# GasSensorCentral_v1_0.net
KiCad netlist of a schematic drawn in EAGLE
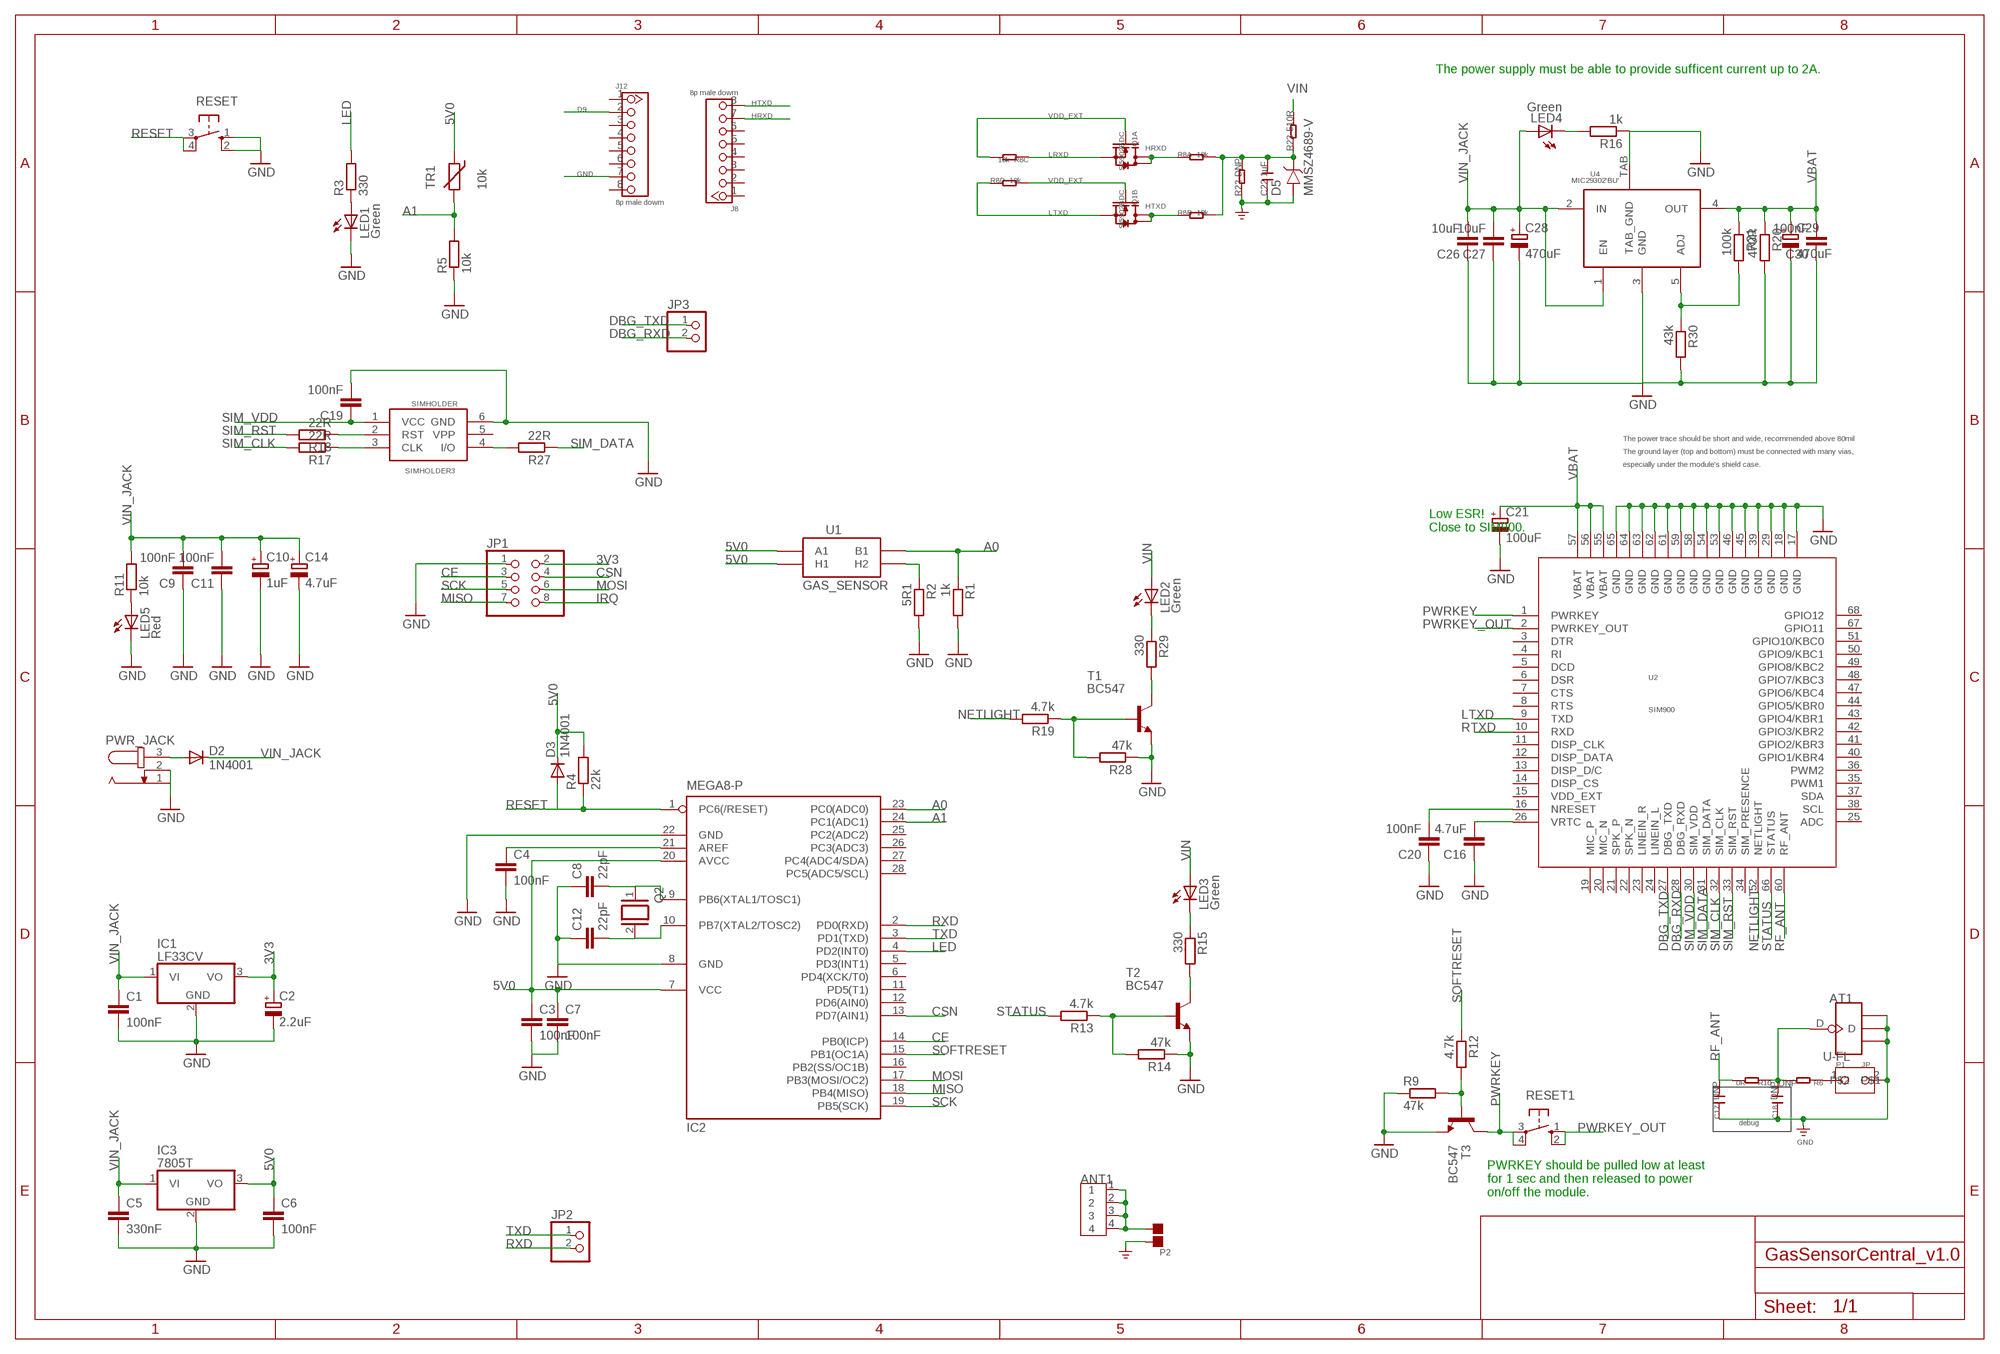
[diagram p0: schematic, sheet 1]

(export (version "E")
  (design (tool "Eeschema 10.0.6"))
  (components
    (comp (ref "ANT1")
      (value "ANTENNA-SMA-IPX")
      (footprint "eagle-import:SMA-TO-IPX")
      (libsource (lib "eagle-import") (part "ANTENNA-SMA-IPX"))
    )
    (comp (ref "AT1")
      (value "U-FL")
      (footprint "eagle-import:4P-U-FL")
      (libsource (lib "eagle-import") (part "ANTENNA-U-FL"))
    )
    (comp (ref "C1")
      (value "100nF")
      (footprint "eagle-import:C025-025X050")
      (libsource (lib "eagle-import") (part "C-EU025-025X050"))
    )
    (comp (ref "C2")
      (value "2.2uF")
      (footprint "eagle-import:E2,5-5")
      (libsource (lib "eagle-import") (part "CPOL-EUE2.5-5"))
    )
    (comp (ref "C3")
      (value "100nF")
      (footprint "eagle-import:C025-025X050")
      (libsource (lib "eagle-import") (part "C-EU025-025X050"))
    )
    (comp (ref "C4")
      (value "100nF")
      (footprint "eagle-import:C025-025X050")
      (libsource (lib "eagle-import") (part "C-EU025-025X050"))
    )
    (comp (ref "C5")
      (value "330nF")
      (footprint "eagle-import:C025-025X050")
      (libsource (lib "eagle-import") (part "C-EU025-025X050"))
    )
    (comp (ref "C6")
      (value "100nF")
      (footprint "eagle-import:C025-025X050")
      (libsource (lib "eagle-import") (part "C-EU025-025X050"))
    )
    (comp (ref "C7")
      (value "100nF")
      (footprint "eagle-import:C025-025X050")
      (libsource (lib "eagle-import") (part "C-EU025-025X050"))
    )
    (comp (ref "C8")
      (value "22pF")
      (footprint "eagle-import:C025-025X050")
      (libsource (lib "eagle-import") (part "C-EU025-025X050"))
    )
    (comp (ref "C9")
      (value "100nF")
      (footprint "eagle-import:C025-025X050")
      (libsource (lib "eagle-import") (part "C-EU025-025X050"))
    )
    (comp (ref "C10")
      (value "1uF")
      (footprint "eagle-import:E2,5-5")
      (libsource (lib "eagle-import") (part "CPOL-EUE2.5-5"))
    )
    (comp (ref "C11")
      (value "100nF")
      (footprint "eagle-import:C025-025X050")
      (libsource (lib "eagle-import") (part "C-EU025-025X050"))
    )
    (comp (ref "C12")
      (value "22pF")
      (footprint "eagle-import:C025-025X050")
      (libsource (lib "eagle-import") (part "C-EU025-025X050"))
    )
    (comp (ref "C14")
      (value "4.7uF")
      (footprint "eagle-import:E2,5-5")
      (libsource (lib "eagle-import") (part "CPOL-EUE2.5-5"))
    )
    (comp (ref "C16")
      (value "4.7uF")
      (footprint "eagle-import:C025-025X050")
      (libsource (lib "eagle-import") (part "C-EU025-025X050"))
    )
    (comp (ref "C17")
      (value "DNP")
      (footprint "eagle-import:0402")
      (libsource (lib "eagle-import") (part "C-0402"))
    )
    (comp (ref "C18")
      (value "DNP")
      (footprint "eagle-import:0402")
      (libsource (lib "eagle-import") (part "C-0402"))
    )
    (comp (ref "C19")
      (value "100nF")
      (footprint "eagle-import:C025-025X050")
      (libsource (lib "eagle-import") (part "C-EU025-025X050"))
    )
    (comp (ref "C20")
      (value "100nF")
      (footprint "eagle-import:C025-025X050")
      (libsource (lib "eagle-import") (part "C-EU025-025X050"))
    )
    (comp (ref "C21")
      (value "100uF")
      (footprint "eagle-import:E2,5-5")
      (libsource (lib "eagle-import") (part "CPOL-EUE2.5-5"))
    )
    (comp (ref "C22")
      (value "1uF")
      (footprint "eagle-import:0603")
      (libsource (lib "eagle-import") (part "C-0603"))
    )
    (comp (ref "C26")
      (value "10uF")
      (footprint "eagle-import:C025-025X050")
      (libsource (lib "eagle-import") (part "C-EU025-025X050"))
    )
    (comp (ref "C27")
      (value "10uF")
      (footprint "eagle-import:C025-025X050")
      (libsource (lib "eagle-import") (part "C-EU025-025X050"))
    )
    (comp (ref "C28")
      (value "470uF")
      (footprint "eagle-import:E2,5-5")
      (libsource (lib "eagle-import") (part "CPOL-EUE2.5-5"))
    )
    (comp (ref "C29")
      (value "470uF")
      (footprint "eagle-import:E2,5-5")
      (libsource (lib "eagle-import") (part "CPOL-EUE2.5-5"))
    )
    (comp (ref "C30")
      (value "100nF")
      (footprint "eagle-import:C025-025X050")
      (libsource (lib "eagle-import") (part "C-EU025-025X050"))
    )
    (comp (ref "D2")
      (value "1N4001")
      (footprint "eagle-import:DO41-10")
      (libsource (lib "eagle-import") (part "1N4004"))
    )
    (comp (ref "D3")
      (value "1N4001")
      (footprint "eagle-import:DO41-10")
      (libsource (lib "eagle-import") (part "1N4004"))
    )
    (comp (ref "D5")
      (value "MMSZ4689-V")
      (footprint "eagle-import:SOD123-2.7X1.6")
      (libsource (lib "eagle-import") (part "D-VOL'MMSZ4681'"))
    )
    (comp (ref "IC1")
      (value "LF33CV")
      (footprint "eagle-import:TO220H")
      (libsource (lib "eagle-import") (part "78T05"))
    )
    (comp (ref "IC2")
      (value "MEGA8-P")
      (footprint "eagle-import:DIL28-3")
      (libsource (lib "eagle-import") (part "MEGA8-P"))
    )
    (comp (ref "IC3")
      (value "7805T")
      (footprint "eagle-import:TO220H")
      (libsource (lib "eagle-import") (part "78T05"))
    )
    (comp (ref "J8")
      (value "8p male dowm")
      (footprint "eagle-import:CK_1X8")
      (libsource (lib "eagle-import") (part "CK_1X8DD"))
    )
    (comp (ref "J12")
      (value "8p male dowm")
      (footprint "eagle-import:CK_1X8")
      (libsource (lib "eagle-import") (part "CK_1X8DD"))
    )
    (comp (ref "JP1")
      (value "PINHD-2X4")
      (footprint "eagle-import:2X04")
      (libsource (lib "eagle-import") (part "PINHD-2X4"))
    )
    (comp (ref "JP2")
      (value "PINHD-1X2/90")
      (footprint "eagle-import:1X02_90")
      (libsource (lib "eagle-import") (part "PINHD-1X2/90"))
    )
    (comp (ref "JP3")
      (value "PINHD-1X2/90")
      (footprint "eagle-import:1X02_90")
      (libsource (lib "eagle-import") (part "PINHD-1X2/90"))
    )
    (comp (ref "LED1")
      (value "Green")
      (footprint "eagle-import:LED3MM")
      (libsource (lib "eagle-import") (part "LED3MM"))
    )
    (comp (ref "LED2")
      (value "Green")
      (footprint "eagle-import:LED3MM")
      (libsource (lib "eagle-import") (part "LED3MM"))
    )
    (comp (ref "LED3")
      (value "Green")
      (footprint "eagle-import:LED3MM")
      (libsource (lib "eagle-import") (part "LED3MM"))
    )
    (comp (ref "LED4")
      (value "Green")
      (footprint "eagle-import:LED3MM")
      (libsource (lib "eagle-import") (part "LED3MM"))
    )
    (comp (ref "LED5")
      (value "Red")
      (footprint "eagle-import:LED3MM")
      (libsource (lib "eagle-import") (part "LED3MM"))
    )
    (comp (ref "P1") (value "JP") (footprint "eagle-import:JP") (libsource (lib "eagle-import") (part "JP")))
    (comp (ref "P2")
      (value "PAD-JUMPER-2P")
      (footprint "eagle-import:2P-SMD-1.78X1.27")
      (fields (field (name "PARTNO") "DNP"))
      (libsource (lib "eagle-import") (part "PAD-JUMPER-2P"))
    )
    (comp (ref "PWR_JACK")
      (value "JACK-PLUG0")
      (footprint "eagle-import:SPC4077")
      (libsource (lib "eagle-import") (part "JACK-PLUG0"))
    )
    (comp (ref "Q1")
      (value "Si5902BDC")
      (footprint "eagle-import:1206-8")
      (libsource (lib "eagle-import") (part "010-DUAL-N-MOSFET_1206-8"))
    )
    (comp (ref "Q2")
      (value "XTAL/S")
      (footprint "eagle-import:QS")
      (libsource (lib "eagle-import") (part "XTAL/S"))
    )
    (comp (ref "R1")
      (value "1k")
      (footprint "eagle-import:0207_10")
      (libsource (lib "eagle-import") (part "R-EU_0207/10"))
    )
    (comp (ref "R2")
      (value "5R1")
      (footprint "eagle-import:0207_10")
      (libsource (lib "eagle-import") (part "R-EU_0207/10"))
    )
    (comp (ref "R3")
      (value "330")
      (footprint "eagle-import:0207_10")
      (libsource (lib "eagle-import") (part "R-EU_0207/10"))
    )
    (comp (ref "R4")
      (value "22k")
      (footprint "eagle-import:0207_10")
      (libsource (lib "eagle-import") (part "R-EU_0207/10"))
    )
    (comp (ref "R5")
      (value "10k")
      (footprint "eagle-import:0207_10")
      (libsource (lib "eagle-import") (part "R-EU_0207/10"))
    )
    (comp (ref "R6")
      (value "DNP")
      (footprint "eagle-import:0402")
      (libsource (lib "eagle-import") (part "R-0402"))
    )
    (comp (ref "R8")
      (value "10k")
      (footprint "eagle-import:1206-8-3.3X2.4")
      (libsource (lib "eagle-import") (part "R-4R-1206"))
    )
    (comp (ref "R9")
      (value "47k")
      (footprint "eagle-import:0207_10")
      (libsource (lib "eagle-import") (part "R-EU_0207/10"))
    )
    (comp (ref "R10")
      (value "0R")
      (footprint "eagle-import:0402")
      (libsource (lib "eagle-import") (part "R-0402"))
    )
    (comp (ref "R11")
      (value "10k")
      (footprint "eagle-import:0207_10")
      (libsource (lib "eagle-import") (part "R-EU_0207/10"))
    )
    (comp (ref "R12")
      (value "4.7k")
      (footprint "eagle-import:0207_10")
      (libsource (lib "eagle-import") (part "R-EU_0207/10"))
    )
    (comp (ref "R13")
      (value "4.7k")
      (footprint "eagle-import:0207_10")
      (libsource (lib "eagle-import") (part "R-EU_0207/10"))
    )
    (comp (ref "R14")
      (value "47k")
      (footprint "eagle-import:0207_10")
      (libsource (lib "eagle-import") (part "R-EU_0207/10"))
    )
    (comp (ref "R15")
      (value "330")
      (footprint "eagle-import:0207_10")
      (libsource (lib "eagle-import") (part "R-EU_0207/10"))
    )
    (comp (ref "R16")
      (value "1k")
      (footprint "eagle-import:0207_10")
      (libsource (lib "eagle-import") (part "R-EU_0207/10"))
    )
    (comp (ref "R17")
      (value "22R")
      (footprint "eagle-import:0207_10")
      (libsource (lib "eagle-import") (part "R-EU_0207/10"))
    )
    (comp (ref "R18")
      (value "22R")
      (footprint "eagle-import:0207_10")
      (libsource (lib "eagle-import") (part "R-EU_0207/10"))
    )
    (comp (ref "R19")
      (value "4.7k")
      (footprint "eagle-import:0207_10")
      (libsource (lib "eagle-import") (part "R-EU_0207/10"))
    )
    (comp (ref "R20")
      (value "470R")
      (footprint "eagle-import:0207_10")
      (libsource (lib "eagle-import") (part "R-EU_0207/10"))
    )
    (comp (ref "R21")
      (value "100k")
      (footprint "eagle-import:0207_10")
      (libsource (lib "eagle-import") (part "R-EU_0207/10"))
    )
    (comp (ref "R22")
      (value "DNP")
      (footprint "eagle-import:0603")
      (libsource (lib "eagle-import") (part "R-0603"))
    )
    (comp (ref "R23")
      (value "510R")
      (footprint "eagle-import:0603")
      (libsource (lib "eagle-import") (part "R-0603"))
    )
    (comp (ref "R27")
      (value "22R")
      (footprint "eagle-import:0207_10")
      (libsource (lib "eagle-import") (part "R-EU_0207/10"))
    )
    (comp (ref "R28")
      (value "47k")
      (footprint "eagle-import:0207_10")
      (libsource (lib "eagle-import") (part "R-EU_0207/10"))
    )
    (comp (ref "R29")
      (value "330")
      (footprint "eagle-import:0207_10")
      (libsource (lib "eagle-import") (part "R-EU_0207/10"))
    )
    (comp (ref "R30")
      (value "43k")
      (footprint "eagle-import:0207_10")
      (libsource (lib "eagle-import") (part "R-EU_0207/10"))
    )
    (comp (ref "RESET")
      (value "10-XX")
      (footprint "eagle-import:B3F-10XX")
      (fields (field (name "MPN") "B3F-1000"))
      (libsource (lib "eagle-import") (part "10-XX"))
    )
    (comp (ref "RESET1")
      (value "10-XX")
      (footprint "eagle-import:B3F-10XX")
      (fields (field (name "MPN") "B3F-1000"))
      (libsource (lib "eagle-import") (part "10-XX"))
    )
    (comp (ref "SIMHOLDER")
      (value "SIMHOLDER3")
      (footprint "eagle-import:SIMHOLDER3")
      (libsource (lib "eagle-import") (part "SIMHOLDER3"))
    )
    (comp (ref "T1")
      (value "BC547")
      (footprint "eagle-import:TO92")
      (libsource (lib "eagle-import") (part "BC547"))
    )
    (comp (ref "T2")
      (value "BC547")
      (footprint "eagle-import:TO92")
      (libsource (lib "eagle-import") (part "BC547"))
    )
    (comp (ref "T3")
      (value "BC547")
      (footprint "eagle-import:TO92")
      (libsource (lib "eagle-import") (part "BC547"))
    )
    (comp (ref "TR1")
      (value "10k")
      (footprint "eagle-import:RS-2,5")
      (libsource (lib "eagle-import") (part "THERMISTOR_R-2,5"))
    )
    (comp (ref "U1")
      (value "GAS_SENSOR")
      (footprint "eagle-import:MQ-3")
      (libsource (lib "eagle-import") (part "GAS_SENSOR"))
    )
    (comp (ref "U2")
      (value "SIM900")
      (footprint "eagle-import:SIM900")
      (libsource (lib "eagle-import") (part "SIM900"))
    )
    (comp (ref "U4")
      (value "MIC29302'BU'")
      (footprint "eagle-import:TO-263")
      (libsource (lib "eagle-import") (part "MIC29302'BU'"))
    )
  )
  (nets
    (net (code "1") (name "/3V3") (class "Default")
      (node (ref "C2") (pin "+") (pinfunction "+_+") (pintype "passive"))
      (node (ref "IC1") (pin "3") (pinfunction "VO_3") (pintype "passive"))
      (node (ref "JP1") (pin "2") (pinfunction "2_2") (pintype "passive"))
    )
    (net (code "2") (name "/5V0") (class "Default")
      (node (ref "C3") (pin "1") (pinfunction "1_1") (pintype "passive"))
      (node (ref "C6") (pin "1") (pinfunction "1_1") (pintype "passive"))
      (node (ref "C7") (pin "1") (pinfunction "1_1") (pintype "passive"))
      (node (ref "D3") (pin "C") (pinfunction "C_C") (pintype "passive"))
      (node (ref "IC2") (pin "20") (pinfunction "AVCC_20") (pintype "power_in"))
      (node (ref "IC2") (pin "7") (pinfunction "VCC_7") (pintype "power_in"))
      (node (ref "IC3") (pin "3") (pinfunction "VO_3") (pintype "passive"))
      (node (ref "R4") (pin "2") (pinfunction "2_2") (pintype "passive"))
      (node (ref "TR1") (pin "1") (pinfunction "1_1") (pintype "passive"))
      (node (ref "U1") (pin "A1") (pinfunction "A1_A1") (pintype "bidirectional"))
      (node (ref "U1") (pin "HA") (pinfunction "H1_HA") (pintype "bidirectional"))
    )
    (net (code "3") (name "/A0") (class "Default")
      (node (ref "IC2") (pin "23") (pinfunction "PC0(ADC0)_23") (pintype "bidirectional"))
      (node (ref "R1") (pin "1") (pinfunction "1_1") (pintype "passive"))
      (node (ref "U1") (pin "B1") (pinfunction "B1_B1") (pintype "bidirectional"))
    )
    (net (code "4") (name "/A1") (class "Default")
      (node (ref "IC2") (pin "24") (pinfunction "PC1(ADC1)_24") (pintype "bidirectional"))
      (node (ref "R5") (pin "2") (pinfunction "2_2") (pintype "passive"))
      (node (ref "TR1") (pin "2") (pinfunction "2_2") (pintype "passive"))
    )
    (net (code "5") (name "/CE") (class "Default")
      (node (ref "IC2") (pin "14") (pinfunction "PB0(ICP)_14") (pintype "bidirectional"))
      (node (ref "JP1") (pin "3") (pinfunction "3_3") (pintype "passive"))
    )
    (net (code "6") (name "/CSN") (class "Default")
      (node (ref "IC2") (pin "13") (pinfunction "PD7(AIN1)_13") (pintype "bidirectional"))
      (node (ref "JP1") (pin "4") (pinfunction "4_4") (pintype "passive"))
    )
    (net (code "7") (name "/D9") (class "Default")
      (node (ref "J12") (pin "2") (pinfunction "P$2_2") (pintype "bidirectional"))
    )
    (net (code "8") (name "/DBG_RXD") (class "Default")
      (node (ref "JP3") (pin "2") (pinfunction "2_2") (pintype "passive"))
      (node (ref "U2") (pin "28") (pinfunction "DBG_RXD_28") (pintype "input"))
    )
    (net (code "9") (name "/DBG_TXD") (class "Default")
      (node (ref "JP3") (pin "1") (pinfunction "1_1") (pintype "passive"))
      (node (ref "U2") (pin "27") (pinfunction "DBG_TXD_27") (pintype "output"))
    )
    (net (code "10") (name "/HRXD") (class "Default")
      (node (ref "J8") (pin "7") (pinfunction "P$7_7") (pintype "bidirectional"))
      (node (ref "Q1") (pin "7") (pinfunction "D_7") (pintype "passive"))
      (node (ref "Q1") (pin "8") (pinfunction "D_8") (pintype "passive"))
      (node (ref "R8") (pin "1") (pinfunction "1_1") (pintype "passive"))
    )
    (net (code "11") (name "/HTXD") (class "Default")
      (node (ref "J8") (pin "8") (pinfunction "P$8_8") (pintype "bidirectional"))
      (node (ref "Q1") (pin "5") (pinfunction "D_5") (pintype "passive"))
      (node (ref "Q1") (pin "6") (pinfunction "D_6") (pintype "passive"))
      (node (ref "R8") (pin "2") (pinfunction "1_2") (pintype "passive"))
    )
    (net (code "12") (name "/IRQ") (class "Default")
      (node (ref "JP1") (pin "8") (pinfunction "8_8") (pintype "passive"))
    )
    (net (code "13") (name "/LED") (class "Default")
      (node (ref "IC2") (pin "4") (pinfunction "PD2(INT0)_4") (pintype "bidirectional"))
      (node (ref "R3") (pin "2") (pinfunction "2_2") (pintype "passive"))
    )
    (net (code "14") (name "/LRXD") (class "Default")
      (node (ref "Q1") (pin "1") (pinfunction "S_1") (pintype "passive"))
      (node (ref "R8") (pin "3") (pinfunction "1_3") (pintype "passive"))
    )
    (net (code "15") (name "/LTXD") (class "Default")
      (node (ref "Q1") (pin "3") (pinfunction "S_3") (pintype "passive"))
      (node (ref "R8") (pin "4") (pinfunction "1_4") (pintype "passive"))
      (node (ref "U2") (pin "9") (pinfunction "TXD_9") (pintype "output"))
    )
    (net (code "16") (name "/MISO") (class "Default")
      (node (ref "IC2") (pin "18") (pinfunction "PB4(MISO)_18") (pintype "bidirectional"))
      (node (ref "JP1") (pin "7") (pinfunction "7_7") (pintype "passive"))
    )
    (net (code "17") (name "/MOSI") (class "Default")
      (node (ref "IC2") (pin "17") (pinfunction "PB3(MOSI/OC2)_17") (pintype "bidirectional"))
      (node (ref "JP1") (pin "6") (pinfunction "6_6") (pintype "passive"))
    )
    (net (code "18") (name "/NETLIGHT") (class "Default")
      (node (ref "R19") (pin "2") (pinfunction "2_2") (pintype "passive"))
      (node (ref "U2") (pin "52") (pinfunction "NETLIGHT_52") (pintype "output"))
    )
    (net (code "19") (name "/PWRKEY") (class "Default")
      (node (ref "RESET1") (pin "3") (pinfunction "P_3") (pintype "passive"))
      (node (ref "RESET1") (pin "4") (pinfunction "P1_4") (pintype "passive"))
      (node (ref "T3") (pin "3") (pinfunction "C_3") (pintype "passive"))
      (node (ref "U2") (pin "1") (pinfunction "PWRKEY_1") (pintype "input"))
    )
    (net (code "20") (name "/PWRKEY_OUT") (class "Default")
      (node (ref "RESET1") (pin "1") (pinfunction "S_1") (pintype "passive"))
      (node (ref "RESET1") (pin "2") (pinfunction "S1_2") (pintype "passive"))
      (node (ref "U2") (pin "2") (pinfunction "PWRKEY_OUT_2") (pintype "output"))
    )
    (net (code "21") (name "/RESET") (class "Default")
      (node (ref "D3") (pin "A") (pinfunction "A_A") (pintype "passive"))
      (node (ref "IC2") (pin "1") (pinfunction "PC6(/RESET)_1") (pintype "bidirectional"))
      (node (ref "R4") (pin "1") (pinfunction "1_1") (pintype "passive"))
      (node (ref "RESET") (pin "3") (pinfunction "P_3") (pintype "passive"))
      (node (ref "RESET") (pin "4") (pinfunction "P1_4") (pintype "passive"))
    )
    (net (code "22") (name "/RF_ANT") (class "Default")
      (node (ref "C17") (pin "2") (pinfunction "2_2") (pintype "passive"))
      (node (ref "R10") (pin "2") (pinfunction "2_2") (pintype "passive"))
      (node (ref "U2") (pin "60") (pinfunction "RF_ANT_60") (pintype "bidirectional"))
    )
    (net (code "23") (name "/RTXD") (class "Default")
      (node (ref "U2") (pin "10") (pinfunction "RXD_10") (pintype "input"))
    )
    (net (code "24") (name "/RXD") (class "Default")
      (node (ref "IC2") (pin "2") (pinfunction "PD0(RXD)_2") (pintype "bidirectional"))
      (node (ref "JP2") (pin "2") (pinfunction "2_2") (pintype "passive"))
    )
    (net (code "25") (name "/SCK") (class "Default")
      (node (ref "IC2") (pin "19") (pinfunction "PB5(SCK)_19") (pintype "bidirectional"))
      (node (ref "JP1") (pin "5") (pinfunction "5_5") (pintype "passive"))
    )
    (net (code "26") (name "/SIM_CLK") (class "Default")
      (node (ref "R17") (pin "2") (pinfunction "2_2") (pintype "passive"))
      (node (ref "U2") (pin "32") (pinfunction "SIM_CLK_32") (pintype "output"))
    )
    (net (code "27") (name "/SIM_DATA") (class "Default")
      (node (ref "R27") (pin "1") (pinfunction "1_1") (pintype "passive"))
      (node (ref "U2") (pin "31") (pinfunction "SIM_DATA_31") (pintype "bidirectional"))
    )
    (net (code "28") (name "/SIM_RST") (class "Default")
      (node (ref "R18") (pin "2") (pinfunction "2_2") (pintype "passive"))
      (node (ref "U2") (pin "33") (pinfunction "SIM_RST_33") (pintype "output"))
    )
    (net (code "29") (name "/SIM_VDD") (class "Default")
      (node (ref "C19") (pin "1") (pinfunction "1_1") (pintype "passive"))
      (node (ref "SIMHOLDER") (pin "1") (pinfunction "VCC_1") (pintype "bidirectional"))
      (node (ref "U2") (pin "30") (pinfunction "SIM_VDD_30") (pintype "output"))
    )
    (net (code "30") (name "/SOFTRESET") (class "Default")
      (node (ref "IC2") (pin "15") (pinfunction "PB1(OC1A)_15") (pintype "bidirectional"))
      (node (ref "R12") (pin "1") (pinfunction "1_1") (pintype "passive"))
    )
    (net (code "31") (name "/STATUS") (class "Default")
      (node (ref "R13") (pin "2") (pinfunction "2_2") (pintype "passive"))
      (node (ref "U2") (pin "66") (pinfunction "STATUS_66") (pintype "output"))
    )
    (net (code "32") (name "/TXD") (class "Default")
      (node (ref "IC2") (pin "3") (pinfunction "PD1(TXD)_3") (pintype "bidirectional"))
      (node (ref "JP2") (pin "1") (pinfunction "1_1") (pintype "passive"))
    )
    (net (code "33") (name "/VBAT") (class "Default")
      (node (ref "C21") (pin "+") (pinfunction "+_+") (pintype "passive"))
      (node (ref "C29") (pin "+") (pinfunction "+_+") (pintype "passive"))
      (node (ref "C30") (pin "2") (pinfunction "2_2") (pintype "passive"))
      (node (ref "R20") (pin "1") (pinfunction "1_1") (pintype "passive"))
      (node (ref "R21") (pin "1") (pinfunction "1_1") (pintype "passive"))
      (node (ref "U2") (pin "55") (pinfunction "VBAT_55") (pintype "power_in"))
      (node (ref "U2") (pin "56") (pinfunction "VBAT_56") (pintype "power_in"))
      (node (ref "U2") (pin "57") (pinfunction "VBAT_57") (pintype "power_in"))
      (node (ref "U4") (pin "4") (pinfunction "OUT_4") (pintype "bidirectional"))
    )
    (net (code "34") (name "/VDD_EXT") (class "Default")
      (node (ref "Q1") (pin "2") (pinfunction "G_2") (pintype "passive"))
      (node (ref "Q1") (pin "4") (pinfunction "G_4") (pintype "passive"))
      (node (ref "R8") (pin "5") (pinfunction "2_5") (pintype "passive"))
      (node (ref "R8") (pin "6") (pinfunction "2_6") (pintype "passive"))
    )
    (net (code "35") (name "/VIN") (class "Default")
      (node (ref "LED2") (pin "A") (pinfunction "A_A") (pintype "passive"))
      (node (ref "LED3") (pin "A") (pinfunction "A_A") (pintype "passive"))
      (node (ref "R23") (pin "2") (pinfunction "2_2") (pintype "passive"))
    )
    (net (code "36") (name "/VIN_JACK") (class "Default")
      (node (ref "C1") (pin "1") (pinfunction "1_1") (pintype "passive"))
      (node (ref "C10") (pin "+") (pinfunction "+_+") (pintype "passive"))
      (node (ref "C11") (pin "2") (pinfunction "2_2") (pintype "passive"))
      (node (ref "C14") (pin "+") (pinfunction "+_+") (pintype "passive"))
      (node (ref "C26") (pin "2") (pinfunction "2_2") (pintype "passive"))
      (node (ref "C27") (pin "2") (pinfunction "2_2") (pintype "passive"))
      (node (ref "C28") (pin "+") (pinfunction "+_+") (pintype "passive"))
      (node (ref "C5") (pin "1") (pinfunction "1_1") (pintype "passive"))
      (node (ref "C9") (pin "2") (pinfunction "2_2") (pintype "passive"))
      (node (ref "D2") (pin "C") (pinfunction "C_C") (pintype "passive"))
      (node (ref "IC1") (pin "1") (pinfunction "VI_1") (pintype "input"))
      (node (ref "IC3") (pin "1") (pinfunction "VI_1") (pintype "input"))
      (node (ref "LED4") (pin "A") (pinfunction "A_A") (pintype "passive"))
      (node (ref "R11") (pin "2") (pinfunction "2_2") (pintype "passive"))
      (node (ref "U4") (pin "1") (pinfunction "EN_1") (pintype "bidirectional"))
      (node (ref "U4") (pin "2") (pinfunction "IN_2") (pintype "bidirectional"))
    )
    (net (code "37") (name "GND") (class "Default")
      (node (ref "AT1") (pin "GND1") (pinfunction "GND1_GND1") (pintype "bidirectional"))
      (node (ref "AT1") (pin "GND2") (pinfunction "GND2_GND2") (pintype "bidirectional"))
      (node (ref "AT1") (pin "GND3") (pinfunction "GND3_GND3") (pintype "bidirectional"))
      (node (ref "C1") (pin "2") (pinfunction "2_2") (pintype "passive"))
      (node (ref "C10") (pin "-") (pinfunction "-_-") (pintype "passive"))
      (node (ref "C11") (pin "1") (pinfunction "1_1") (pintype "passive"))
      (node (ref "C12") (pin "1") (pinfunction "1_1") (pintype "passive"))
      (node (ref "C14") (pin "-") (pinfunction "-_-") (pintype "passive"))
      (node (ref "C16") (pin "1") (pinfunction "1_1") (pintype "passive"))
      (node (ref "C17") (pin "1") (pinfunction "1_1") (pintype "passive"))
      (node (ref "C18") (pin "1") (pinfunction "1_1") (pintype "passive"))
      (node (ref "C19") (pin "2") (pinfunction "2_2") (pintype "passive"))
      (node (ref "C2") (pin "-") (pinfunction "-_-") (pintype "passive"))
      (node (ref "C20") (pin "1") (pinfunction "1_1") (pintype "passive"))
      (node (ref "C21") (pin "-") (pinfunction "-_-") (pintype "passive"))
      (node (ref "C22") (pin "1") (pinfunction "1_1") (pintype "passive"))
      (node (ref "C26") (pin "1") (pinfunction "1_1") (pintype "passive"))
      (node (ref "C27") (pin "1") (pinfunction "1_1") (pintype "passive"))
      (node (ref "C28") (pin "-") (pinfunction "-_-") (pintype "passive"))
      (node (ref "C29") (pin "-") (pinfunction "-_-") (pintype "passive"))
      (node (ref "C3") (pin "2") (pinfunction "2_2") (pintype "passive"))
      (node (ref "C30") (pin "1") (pinfunction "1_1") (pintype "passive"))
      (node (ref "C4") (pin "2") (pinfunction "2_2") (pintype "passive"))
      (node (ref "C5") (pin "2") (pinfunction "2_2") (pintype "passive"))
      (node (ref "C6") (pin "2") (pinfunction "2_2") (pintype "passive"))
      (node (ref "C7") (pin "2") (pinfunction "2_2") (pintype "passive"))
      (node (ref "C8") (pin "1") (pinfunction "1_1") (pintype "passive"))
      (node (ref "C9") (pin "1") (pinfunction "1_1") (pintype "passive"))
      (node (ref "D5") (pin "1") (pinfunction "1_1") (pintype "bidirectional"))
      (node (ref "IC1") (pin "2") (pinfunction "GND_2") (pintype "passive"))
      (node (ref "IC2") (pin "22") (pinfunction "GND_22") (pintype "power_in"))
      (node (ref "IC2") (pin "8") (pinfunction "GND_8") (pintype "power_in"))
      (node (ref "IC3") (pin "2") (pinfunction "GND_2") (pintype "passive"))
      (node (ref "J12") (pin "7") (pinfunction "P$7_7") (pintype "bidirectional"))
      (node (ref "JP1") (pin "1") (pinfunction "1_1") (pintype "passive"))
      (node (ref "LED1") (pin "K") (pinfunction "C_K") (pintype "passive"))
      (node (ref "LED5") (pin "K") (pinfunction "C_K") (pintype "passive"))
      (node (ref "P1") (pin "2") (pinfunction "P$2_2") (pintype "bidirectional"))
      (node (ref "P2") (pin "2") (pinfunction "2_2") (pintype "bidirectional"))
      (node (ref "PWR_JACK") (pin "1") (pinfunction "1_1") (pintype "passive"))
      (node (ref "PWR_JACK") (pin "2") (pinfunction "2_2") (pintype "passive"))
      (node (ref "R1") (pin "2") (pinfunction "2_2") (pintype "passive"))
      (node (ref "R14") (pin "1") (pinfunction "1_1") (pintype "passive"))
      (node (ref "R16") (pin "1") (pinfunction "1_1") (pintype "passive"))
      (node (ref "R2") (pin "2") (pinfunction "2_2") (pintype "passive"))
      (node (ref "R20") (pin "2") (pinfunction "2_2") (pintype "passive"))
      (node (ref "R22") (pin "1") (pinfunction "1_1") (pintype "passive"))
      (node (ref "R28") (pin "1") (pinfunction "1_1") (pintype "passive"))
      (node (ref "R30") (pin "2") (pinfunction "2_2") (pintype "passive"))
      (node (ref "R5") (pin "1") (pinfunction "1_1") (pintype "passive"))
      (node (ref "R9") (pin "1") (pinfunction "1_1") (pintype "passive"))
      (node (ref "RESET") (pin "1") (pinfunction "S_1") (pintype "passive"))
      (node (ref "RESET") (pin "2") (pinfunction "S1_2") (pintype "passive"))
      (node (ref "SIMHOLDER") (pin "6") (pinfunction "GND_6") (pintype "bidirectional"))
      (node (ref "T1") (pin "1") (pinfunction "E_1") (pintype "passive"))
      (node (ref "T2") (pin "1") (pinfunction "E_1") (pintype "passive"))
      (node (ref "T3") (pin "1") (pinfunction "E_1") (pintype "passive"))
      (node (ref "U2") (pin "17") (pinfunction "GND_17") (pintype "power_in"))
      (node (ref "U2") (pin "18") (pinfunction "GND_18") (pintype "power_in"))
      (node (ref "U2") (pin "29") (pinfunction "GND_29") (pintype "power_in"))
      (node (ref "U2") (pin "39") (pinfunction "GND_39") (pintype "power_in"))
      (node (ref "U2") (pin "45") (pinfunction "GND_45") (pintype "power_in"))
      (node (ref "U2") (pin "46") (pinfunction "GND_46") (pintype "power_in"))
      (node (ref "U2") (pin "53") (pinfunction "GND_53") (pintype "power_in"))
      (node (ref "U2") (pin "54") (pinfunction "GND_54") (pintype "power_in"))
      (node (ref "U2") (pin "58") (pinfunction "GND_58") (pintype "power_in"))
      (node (ref "U2") (pin "59") (pinfunction "GND_59") (pintype "power_in"))
      (node (ref "U2") (pin "61") (pinfunction "GND_61") (pintype "power_in"))
      (node (ref "U2") (pin "62") (pinfunction "GND_62") (pintype "power_in"))
      (node (ref "U2") (pin "63") (pinfunction "GND_63") (pintype "power_in"))
      (node (ref "U2") (pin "64") (pinfunction "GND_64") (pintype "power_in"))
      (node (ref "U2") (pin "65") (pinfunction "GND_65") (pintype "power_in"))
      (node (ref "U4") (pin "3") (pinfunction "GND_3") (pintype "bidirectional"))
      (node (ref "U4") (pin "TAB") (pinfunction "TAB_GND_TAB") (pintype "bidirectional"))
    )
    (net (code "38") (name "Net-(ANT1-Pad1)") (class "Default")
      (node (ref "ANT1") (pin "1") (pinfunction "1_1") (pintype "bidirectional"))
      (node (ref "ANT1") (pin "2") (pinfunction "2_2") (pintype "bidirectional"))
      (node (ref "ANT1") (pin "3") (pinfunction "3_3") (pintype "bidirectional"))
      (node (ref "ANT1") (pin "4") (pinfunction "4_4") (pintype "bidirectional"))
      (node (ref "P2") (pin "1") (pinfunction "1_1") (pintype "bidirectional"))
    )
    (net (code "39") (name "Net-(AT1-PadD)") (class "Default")
      (node (ref "AT1") (pin "D") (pinfunction "D_D") (pintype "bidirectional"))
      (node (ref "C18") (pin "2") (pinfunction "2_2") (pintype "passive"))
      (node (ref "R10") (pin "1") (pinfunction "1_1") (pintype "passive"))
      (node (ref "R6") (pin "2") (pinfunction "2_2") (pintype "passive"))
    )
    (net (code "40") (name "Net-(D2-PadA)") (class "Default")
      (node (ref "D2") (pin "A") (pinfunction "A_A") (pintype "passive"))
      (node (ref "PWR_JACK") (pin "3") (pinfunction "3_3") (pintype "passive"))
    )
    (net (code "41") (name "Net-(IC2-AREF)") (class "Default")
      (node (ref "C4") (pin "1") (pinfunction "1_1") (pintype "passive"))
      (node (ref "IC2") (pin "21") (pinfunction "AREF_21") (pintype "passive"))
    )
    (net (code "42") (name "Net-(IC2-PB6(XTAL1{slash}TOSC1))") (class "Default")
      (node (ref "C8") (pin "2") (pinfunction "2_2") (pintype "passive"))
      (node (ref "IC2") (pin "9") (pinfunction "PB6(XTAL1/TOSC1)_9") (pintype "bidirectional"))
      (node (ref "Q2") (pin "1") (pinfunction "1_1") (pintype "passive"))
    )
    (net (code "43") (name "Net-(IC2-PB7(XTAL2{slash}TOSC2))") (class "Default")
      (node (ref "C12") (pin "2") (pinfunction "2_2") (pintype "passive"))
      (node (ref "IC2") (pin "10") (pinfunction "PB7(XTAL2/TOSC2)_10") (pintype "bidirectional"))
      (node (ref "Q2") (pin "2") (pinfunction "2_2") (pintype "passive"))
    )
    (net (code "44") (name "Net-(LED1-PadA)") (class "Default")
      (node (ref "LED1") (pin "A") (pinfunction "A_A") (pintype "passive"))
      (node (ref "R3") (pin "1") (pinfunction "1_1") (pintype "passive"))
    )
    (net (code "45") (name "Net-(LED2-C)") (class "Default")
      (node (ref "LED2") (pin "K") (pinfunction "C_K") (pintype "passive"))
      (node (ref "R29") (pin "1") (pinfunction "1_1") (pintype "passive"))
    )
    (net (code "46") (name "Net-(LED3-C)") (class "Default")
      (node (ref "LED3") (pin "K") (pinfunction "C_K") (pintype "passive"))
      (node (ref "R15") (pin "1") (pinfunction "1_1") (pintype "passive"))
    )
    (net (code "47") (name "Net-(LED4-C)") (class "Default")
      (node (ref "LED4") (pin "K") (pinfunction "C_K") (pintype "passive"))
      (node (ref "R16") (pin "2") (pinfunction "2_2") (pintype "passive"))
    )
    (net (code "48") (name "Net-(LED5-PadA)") (class "Default")
      (node (ref "LED5") (pin "A") (pinfunction "A_A") (pintype "passive"))
      (node (ref "R11") (pin "1") (pinfunction "1_1") (pintype "passive"))
    )
    (net (code "49") (name "Net-(P1-P$1)") (class "Default")
      (node (ref "P1") (pin "1") (pinfunction "P$1_1") (pintype "bidirectional"))
      (node (ref "R6") (pin "1") (pinfunction "1_1") (pintype "passive"))
    )
    (net (code "50") (name "Net-(R8A-2)") (class "Default")
      (node (ref "C22") (pin "2") (pinfunction "2_2") (pintype "passive"))
      (node (ref "D5") (pin "2") (pinfunction "2_2") (pintype "bidirectional"))
      (node (ref "R22") (pin "2") (pinfunction "2_2") (pintype "passive"))
      (node (ref "R23") (pin "1") (pinfunction "1_1") (pintype "passive"))
      (node (ref "R8") (pin "7") (pinfunction "2_7") (pintype "passive"))
      (node (ref "R8") (pin "8") (pinfunction "2_8") (pintype "passive"))
    )
    (net (code "51") (name "Net-(SIMHOLDER-CLK)") (class "Default")
      (node (ref "R17") (pin "1") (pinfunction "1_1") (pintype "passive"))
      (node (ref "SIMHOLDER") (pin "3") (pinfunction "CLK_3") (pintype "bidirectional"))
    )
    (net (code "52") (name "Net-(SIMHOLDER-I{slash}O)") (class "Default")
      (node (ref "R27") (pin "2") (pinfunction "2_2") (pintype "passive"))
      (node (ref "SIMHOLDER") (pin "4") (pinfunction "I/O_4") (pintype "bidirectional"))
    )
    (net (code "53") (name "Net-(SIMHOLDER-RST)") (class "Default")
      (node (ref "R18") (pin "1") (pinfunction "1_1") (pintype "passive"))
      (node (ref "SIMHOLDER") (pin "2") (pinfunction "RST_2") (pintype "bidirectional"))
    )
    (net (code "54") (name "Net-(T1-B)") (class "Default")
      (node (ref "R19") (pin "1") (pinfunction "1_1") (pintype "passive"))
      (node (ref "R28") (pin "2") (pinfunction "2_2") (pintype "passive"))
      (node (ref "T1") (pin "2") (pinfunction "B_2") (pintype "passive"))
    )
    (net (code "55") (name "Net-(T1-C)") (class "Default")
      (node (ref "R29") (pin "2") (pinfunction "2_2") (pintype "passive"))
      (node (ref "T1") (pin "3") (pinfunction "C_3") (pintype "passive"))
    )
    (net (code "56") (name "Net-(T2-B)") (class "Default")
      (node (ref "R13") (pin "1") (pinfunction "1_1") (pintype "passive"))
      (node (ref "R14") (pin "2") (pinfunction "2_2") (pintype "passive"))
      (node (ref "T2") (pin "2") (pinfunction "B_2") (pintype "passive"))
    )
    (net (code "57") (name "Net-(T2-C)") (class "Default")
      (node (ref "R15") (pin "2") (pinfunction "2_2") (pintype "passive"))
      (node (ref "T2") (pin "3") (pinfunction "C_3") (pintype "passive"))
    )
    (net (code "58") (name "Net-(T3-B)") (class "Default")
      (node (ref "R12") (pin "2") (pinfunction "2_2") (pintype "passive"))
      (node (ref "R9") (pin "2") (pinfunction "2_2") (pintype "passive"))
      (node (ref "T3") (pin "2") (pinfunction "B_2") (pintype "passive"))
    )
    (net (code "59") (name "Net-(U1-H2)") (class "Default")
      (node (ref "R2") (pin "1") (pinfunction "1_1") (pintype "passive"))
      (node (ref "U1") (pin "HB") (pinfunction "H2_HB") (pintype "bidirectional"))
    )
    (net (code "60") (name "Net-(U2-NRESET)") (class "Default")
      (node (ref "C20") (pin "2") (pinfunction "2_2") (pintype "passive"))
      (node (ref "U2") (pin "16") (pinfunction "NRESET_16") (pintype "input"))
    )
    (net (code "61") (name "Net-(U2-VRTC)") (class "Default")
      (node (ref "C16") (pin "2") (pinfunction "2_2") (pintype "passive"))
      (node (ref "U2") (pin "26") (pinfunction "VRTC_26") (pintype "bidirectional"))
    )
    (net (code "62") (name "Net-(U4-ADJ)") (class "Default")
      (node (ref "R21") (pin "2") (pinfunction "2_2") (pintype "passive"))
      (node (ref "R30") (pin "1") (pinfunction "1_1") (pintype "passive"))
      (node (ref "U4") (pin "5") (pinfunction "ADJ_5") (pintype "bidirectional"))
    )
    (net (code "63") (name "unconnected-(IC2-PB2(SS{slash}OC1B)-Pad16)") (class "Default")
      (node (ref "IC2") (pin "16") (pinfunction "PB2(SS/OC1B)_16") (pintype "bidirectional"))
    )
    (net (code "64") (name "unconnected-(IC2-PC2(ADC2)-Pad25)") (class "Default")
      (node (ref "IC2") (pin "25") (pinfunction "PC2(ADC2)_25") (pintype "bidirectional"))
    )
    (net (code "65") (name "unconnected-(IC2-PC3(ADC3)-Pad26)") (class "Default")
      (node (ref "IC2") (pin "26") (pinfunction "PC3(ADC3)_26") (pintype "bidirectional"))
    )
    (net (code "66") (name "unconnected-(IC2-PC4(ADC4{slash}SDA)-Pad27)") (class "Default")
      (node (ref "IC2") (pin "27") (pinfunction "PC4(ADC4/SDA)_27") (pintype "bidirectional"))
    )
    (net (code "67") (name "unconnected-(IC2-PC5(ADC5{slash}SCL)-Pad28)") (class "Default")
      (node (ref "IC2") (pin "28") (pinfunction "PC5(ADC5/SCL)_28") (pintype "bidirectional"))
    )
    (net (code "68") (name "unconnected-(IC2-PD3(INT1)-Pad5)") (class "Default")
      (node (ref "IC2") (pin "5") (pinfunction "PD3(INT1)_5") (pintype "bidirectional"))
    )
    (net (code "69") (name "unconnected-(IC2-PD4(XCK{slash}T0)-Pad6)") (class "Default")
      (node (ref "IC2") (pin "6") (pinfunction "PD4(XCK/T0)_6") (pintype "bidirectional"))
    )
    (net (code "70") (name "unconnected-(IC2-PD5(T1)-Pad11)") (class "Default")
      (node (ref "IC2") (pin "11") (pinfunction "PD5(T1)_11") (pintype "bidirectional"))
    )
    (net (code "71") (name "unconnected-(IC2-PD6(AIN0)-Pad12)") (class "Default")
      (node (ref "IC2") (pin "12") (pinfunction "PD6(AIN0)_12") (pintype "bidirectional"))
    )
    (net (code "72") (name "unconnected-(J8-P$1-Pad1)") (class "Default")
      (node (ref "J8") (pin "1") (pinfunction "P$1_1") (pintype "bidirectional"))
    )
    (net (code "73") (name "unconnected-(J8-P$2-Pad2)") (class "Default")
      (node (ref "J8") (pin "2") (pinfunction "P$2_2") (pintype "bidirectional"))
    )
    (net (code "74") (name "unconnected-(J8-P$3-Pad3)") (class "Default")
      (node (ref "J8") (pin "3") (pinfunction "P$3_3") (pintype "bidirectional"))
    )
    (net (code "75") (name "unconnected-(J8-P$4-Pad4)") (class "Default")
      (node (ref "J8") (pin "4") (pinfunction "P$4_4") (pintype "bidirectional"))
    )
    (net (code "76") (name "unconnected-(J8-P$5-Pad5)") (class "Default")
      (node (ref "J8") (pin "5") (pinfunction "P$5_5") (pintype "bidirectional"))
    )
    (net (code "77") (name "unconnected-(J8-P$6-Pad6)") (class "Default")
      (node (ref "J8") (pin "6") (pinfunction "P$6_6") (pintype "bidirectional"))
    )
    (net (code "78") (name "unconnected-(J12-P$1-Pad1)") (class "Default")
      (node (ref "J12") (pin "1") (pinfunction "P$1_1") (pintype "bidirectional"))
    )
    (net (code "79") (name "unconnected-(J12-P$3-Pad3)") (class "Default")
      (node (ref "J12") (pin "3") (pinfunction "P$3_3") (pintype "bidirectional"))
    )
    (net (code "80") (name "unconnected-(J12-P$4-Pad4)") (class "Default")
      (node (ref "J12") (pin "4") (pinfunction "P$4_4") (pintype "bidirectional"))
    )
    (net (code "81") (name "unconnected-(J12-P$5-Pad5)") (class "Default")
      (node (ref "J12") (pin "5") (pinfunction "P$5_5") (pintype "bidirectional"))
    )
    (net (code "82") (name "unconnected-(J12-P$6-Pad6)") (class "Default")
      (node (ref "J12") (pin "6") (pinfunction "P$6_6") (pintype "bidirectional"))
    )
    (net (code "83") (name "unconnected-(J12-P$8-Pad8)") (class "Default")
      (node (ref "J12") (pin "8") (pinfunction "P$8_8") (pintype "bidirectional"))
    )
    (net (code "84") (name "unconnected-(SIMHOLDER-VPP-Pad5)") (class "Default")
      (node (ref "SIMHOLDER") (pin "5") (pinfunction "VPP_5") (pintype "bidirectional"))
    )
    (net (code "85") (name "unconnected-(U2-ADC-Pad25)") (class "Default")
      (node (ref "U2") (pin "25") (pinfunction "ADC_25") (pintype "input"))
    )
    (net (code "86") (name "unconnected-(U2-CTS-Pad7)") (class "Default")
      (node (ref "U2") (pin "7") (pinfunction "CTS_7") (pintype "output"))
    )
    (net (code "87") (name "unconnected-(U2-DCD-Pad5)") (class "Default")
      (node (ref "U2") (pin "5") (pinfunction "DCD_5") (pintype "output"))
    )
    (net (code "88") (name "unconnected-(U2-DISP_CLK-Pad11)") (class "Default")
      (node (ref "U2") (pin "11") (pinfunction "DISP_CLK_11") (pintype "output"))
    )
    (net (code "89") (name "unconnected-(U2-DISP_CS-Pad14)") (class "Default")
      (node (ref "U2") (pin "14") (pinfunction "DISP_CS_14") (pintype "output"))
    )
    (net (code "90") (name "unconnected-(U2-DISP_DATA-Pad12)") (class "Default")
      (node (ref "U2") (pin "12") (pinfunction "DISP_DATA_12") (pintype "bidirectional"))
    )
    (net (code "91") (name "unconnected-(U2-DISP_D{slash}C-Pad13)") (class "Default")
      (node (ref "U2") (pin "13") (pinfunction "DISP_D/C_13") (pintype "output"))
    )
    (net (code "92") (name "unconnected-(U2-DSR-Pad6)") (class "Default")
      (node (ref "U2") (pin "6") (pinfunction "DSR_6") (pintype "output"))
    )
    (net (code "93") (name "unconnected-(U2-DTR-Pad3)") (class "Default")
      (node (ref "U2") (pin "3") (pinfunction "DTR_3") (pintype "input"))
    )
    (net (code "94") (name "unconnected-(U2-GPIO1{slash}KBR4-Pad40)") (class "Default")
      (node (ref "U2") (pin "40") (pinfunction "GPIO1/KBR4_40") (pintype "output"))
    )
    (net (code "95") (name "unconnected-(U2-GPIO2{slash}KBR3-Pad41)") (class "Default")
      (node (ref "U2") (pin "41") (pinfunction "GPIO2/KBR3_41") (pintype "output"))
    )
    (net (code "96") (name "unconnected-(U2-GPIO3{slash}KBR2-Pad42)") (class "Default")
      (node (ref "U2") (pin "42") (pinfunction "GPIO3/KBR2_42") (pintype "output"))
    )
    (net (code "97") (name "unconnected-(U2-GPIO4{slash}KBR1-Pad43)") (class "Default")
      (node (ref "U2") (pin "43") (pinfunction "GPIO4/KBR1_43") (pintype "output"))
    )
    (net (code "98") (name "unconnected-(U2-GPIO5{slash}KBR0-Pad44)") (class "Default")
      (node (ref "U2") (pin "44") (pinfunction "GPIO5/KBR0_44") (pintype "output"))
    )
    (net (code "99") (name "unconnected-(U2-GPIO6{slash}KBC4-Pad47)") (class "Default")
      (node (ref "U2") (pin "47") (pinfunction "GPIO6/KBC4_47") (pintype "input"))
    )
    (net (code "100") (name "unconnected-(U2-GPIO7{slash}KBC3-Pad48)") (class "Default")
      (node (ref "U2") (pin "48") (pinfunction "GPIO7/KBC3_48") (pintype "bidirectional"))
    )
    (net (code "101") (name "unconnected-(U2-GPIO8{slash}KBC2-Pad49)") (class "Default")
      (node (ref "U2") (pin "49") (pinfunction "GPIO8/KBC2_49") (pintype "input"))
    )
    (net (code "102") (name "unconnected-(U2-GPIO9{slash}KBC1-Pad50)") (class "Default")
      (node (ref "U2") (pin "50") (pinfunction "GPIO9/KBC1_50") (pintype "input"))
    )
    (net (code "103") (name "unconnected-(U2-GPIO10{slash}KBC0-Pad51)") (class "Default")
      (node (ref "U2") (pin "51") (pinfunction "GPIO10/KBC0_51") (pintype "bidirectional"))
    )
    (net (code "104") (name "unconnected-(U2-GPIO11-Pad67)") (class "Default")
      (node (ref "U2") (pin "67") (pinfunction "GPIO11_67") (pintype "bidirectional"))
    )
    (net (code "105") (name "unconnected-(U2-GPIO12-Pad68)") (class "Default")
      (node (ref "U2") (pin "68") (pinfunction "GPIO12_68") (pintype "bidirectional"))
    )
    (net (code "106") (name "unconnected-(U2-LINEIN_L-Pad24)") (class "Default")
      (node (ref "U2") (pin "24") (pinfunction "LINEIN_L_24") (pintype "input"))
    )
    (net (code "107") (name "unconnected-(U2-LINEIN_R-Pad23)") (class "Default")
      (node (ref "U2") (pin "23") (pinfunction "LINEIN_R_23") (pintype "input"))
    )
    (net (code "108") (name "unconnected-(U2-MIC_N-Pad20)") (class "Default")
      (node (ref "U2") (pin "20") (pinfunction "MIC_N_20") (pintype "input"))
    )
    (net (code "109") (name "unconnected-(U2-MIC_P-Pad19)") (class "Default")
      (node (ref "U2") (pin "19") (pinfunction "MIC_P_19") (pintype "input"))
    )
    (net (code "110") (name "unconnected-(U2-PWM1-Pad35)") (class "Default")
      (node (ref "U2") (pin "35") (pinfunction "PWM1_35") (pintype "output"))
    )
    (net (code "111") (name "unconnected-(U2-PWM2-Pad36)") (class "Default")
      (node (ref "U2") (pin "36") (pinfunction "PWM2_36") (pintype "output"))
    )
    (net (code "112") (name "unconnected-(U2-RI-Pad4)") (class "Default")
      (node (ref "U2") (pin "4") (pinfunction "RI_4") (pintype "output"))
    )
    (net (code "113") (name "unconnected-(U2-RTS-Pad8)") (class "Default")
      (node (ref "U2") (pin "8") (pinfunction "RTS_8") (pintype "input"))
    )
    (net (code "114") (name "unconnected-(U2-SCL-Pad38)") (class "Default")
      (node (ref "U2") (pin "38") (pinfunction "SCL_38") (pintype "output"))
    )
    (net (code "115") (name "unconnected-(U2-SDA-Pad37)") (class "Default")
      (node (ref "U2") (pin "37") (pinfunction "SDA_37") (pintype "bidirectional"))
    )
    (net (code "116") (name "unconnected-(U2-SIM_PRESENCE-Pad34)") (class "Default")
      (node (ref "U2") (pin "34") (pinfunction "SIM_PRESENCE_34") (pintype "input"))
    )
    (net (code "117") (name "unconnected-(U2-SPK_N-Pad22)") (class "Default")
      (node (ref "U2") (pin "22") (pinfunction "SPK_N_22") (pintype "output"))
    )
    (net (code "118") (name "unconnected-(U2-SPK_P-Pad21)") (class "Default")
      (node (ref "U2") (pin "21") (pinfunction "SPK_P_21") (pintype "output"))
    )
    (net (code "119") (name "unconnected-(U2-VDD_EXT-Pad15)") (class "Default")
      (node (ref "U2") (pin "15") (pinfunction "VDD_EXT_15") (pintype "output"))
    )
  )
)
